# Environmental_Sensor.net
KiCad netlist of a schematic drawn in Altium Designer
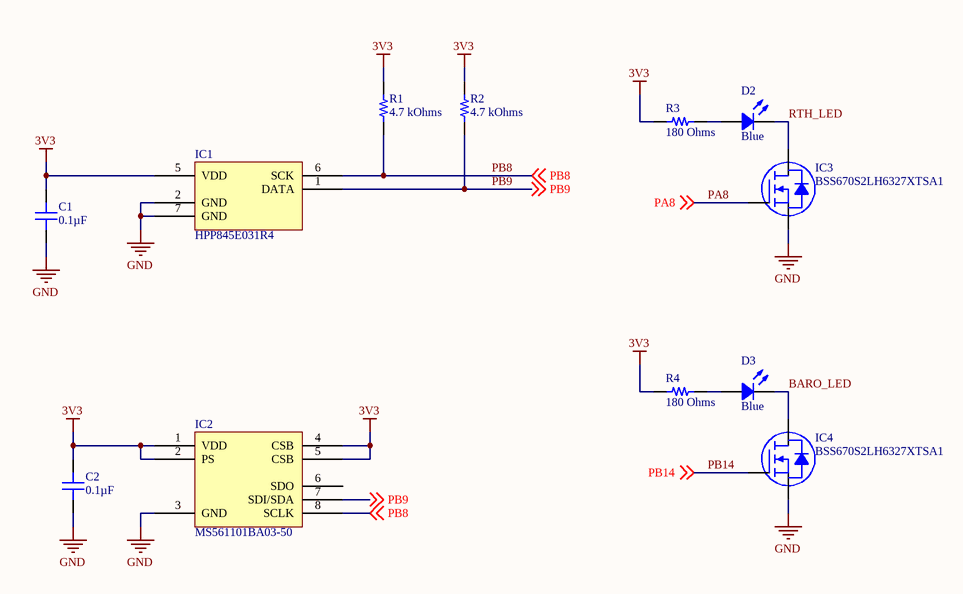
[diagram p0: Environmental Sensor.SchDoc]

(export (version "E")
  (design (tool "Eeschema 10.0.6"))
  (components
    (comp (ref "C1")
      (value "0.1µF")
      (footprint "CAP 0603_1608")
      (description "CAP CER 0.1UF 50V X7R 0603")
      (fields (field (name "PART NUMBER") "06035C104JAT4A") (field (name "MANUFACTURER") "AVX Corporation"))
      (libsource (lib "altiumlibrary.com") (part "Capacitor"))
    )
    (comp (ref "C2")
      (value "0.1µF")
      (footprint "CAP 0603_1608")
      (description "CAP CER 0.1UF 50V X7R 0603")
      (fields (field (name "PART NUMBER") "06035C104JAT4A") (field (name "MANUFACTURER") "AVX Corporation"))
      (libsource (lib "altiumlibrary.com") (part "Capacitor"))
    )
    (comp (ref "D2")
      (value "Blue")
      (footprint "LED 0603_1608 BLUE")
      (description "LED BLUE CLEAR CHIP SMD")
      (fields (field (name "PART NUMBER") "LTST-C193TBKT-5A") (field (name "MANUFACTURER") "Lite-On Inc."))
      (libsource (lib "altiumlibrary.com") (part "LED"))
    )
    (comp (ref "D3")
      (value "Blue")
      (footprint "LED 0603_1608 BLUE")
      (description "LED BLUE CLEAR CHIP SMD")
      (fields (field (name "PART NUMBER") "LTST-C193TBKT-5A") (field (name "MANUFACTURER") "Lite-On Inc."))
      (libsource (lib "altiumlibrary.com") (part "LED"))
    )
    (comp (ref "IC1")
      (value "HPP845E031R4")
      (footprint "TE HPP845E031R4")
      (description "SENSOR HUMID/TEMP 3V I2C 2% SMD")
      (fields (field (name "MANUFACTURER") "TE Connectivity Measurement Specialties"))
      (libsource (lib "altiumlibrary.com") (part "TE HPP845E031R4"))
    )
    (comp (ref "IC2")
      (value "MS561101BA03-50")
      (footprint "MEAS SPEC MS5611-01BA03")
      (description "BAROMETRIC PRESSURE SENSOR")
      (fields (field (name "MANUFACTURER") "TE Connectivity Measurement Specialties"))
      (libsource (lib "altiumlibrary.com") (part "MEAS SPEC MS5611"))
    )
    (comp (ref "IC3")
      (value "BSS670S2LH6327XTSA1")
      (footprint "INFINEON SOT-23-3")
      (description "MOSFET N-CH 55V 540MA SOT23")
      (fields (field (name "MANUFACTURER") "Infineon Technologies"))
      (libsource (lib "altiumlibrary.com") (part "INFINEON MOSFET N-CH SOT-23-3 GSD"))
    )
    (comp (ref "IC4")
      (value "BSS670S2LH6327XTSA1")
      (footprint "INFINEON SOT-23-3")
      (description "MOSFET N-CH 55V 540MA SOT23")
      (fields (field (name "MANUFACTURER") "Infineon Technologies"))
      (libsource (lib "altiumlibrary.com") (part "INFINEON MOSFET N-CH SOT-23-3 GSD"))
    )
    (comp (ref "R1")
      (value "4.7 kOhms")
      (footprint "RES 0603_1608")
      (description "RES SMD 4.7K OHM 1% 1/10W 0603")
      (fields
        (field (name "PART NUMBER") "ERJ-3EKF4701V")
        (field (name "MANUFACTURER") "Panasonic Electronic Components")
      )
      (libsource (lib "altiumlibrary.com") (part "Resistor"))
    )
    (comp (ref "R2")
      (value "4.7 kOhms")
      (footprint "RES 0603_1608")
      (description "RES SMD 4.7K OHM 1% 1/10W 0603")
      (fields
        (field (name "PART NUMBER") "ERJ-3EKF4701V")
        (field (name "MANUFACTURER") "Panasonic Electronic Components")
      )
      (libsource (lib "altiumlibrary.com") (part "Resistor"))
    )
    (comp (ref "R3")
      (value "180 Ohms")
      (footprint "RES 0603_1608")
      (description "RES SMD 180 OHM 5% 1/4W 0603")
      (fields
        (field (name "PART NUMBER") "ERJ-PA3J181V")
        (field (name "MANUFACTURER") "Panasonic Electronic Components")
      )
      (libsource (lib "altiumlibrary.com") (part "Resistor"))
    )
    (comp (ref "R4")
      (value "180 Ohms")
      (footprint "RES 0603_1608")
      (description "RES SMD 180 OHM 5% 1/4W 0603")
      (fields
        (field (name "PART NUMBER") "ERJ-PA3J181V")
        (field (name "MANUFACTURER") "Panasonic Electronic Components")
      )
      (libsource (lib "altiumlibrary.com") (part "Resistor"))
    )
  )
  (nets
    (net (code "1") (name "/BARO_LED") (class "Default")
      (node (ref "D3") (pin "2") (pinfunction "2_2") (pintype "passive"))
      (node (ref "IC4") (pin "3") (pinfunction "D_3") (pintype "passive"))
    )
    (net (code "2") (name "/RTH_LED") (class "Default")
      (node (ref "D2") (pin "2") (pinfunction "2_2") (pintype "passive"))
      (node (ref "IC3") (pin "3") (pinfunction "D_3") (pintype "passive"))
    )
    (net (code "3") (name "3V3") (class "Default")
      (node (ref "C1") (pin "2") (pinfunction "2_2") (pintype "passive"))
      (node (ref "C2") (pin "2") (pinfunction "2_2") (pintype "passive"))
      (node (ref "IC1") (pin "5") (pinfunction "VDD_5") (pintype "passive"))
      (node (ref "IC2") (pin "1") (pinfunction "VDD_1") (pintype "passive"))
      (node (ref "IC2") (pin "2") (pinfunction "PS_2") (pintype "passive"))
      (node (ref "IC2") (pin "4") (pinfunction "CSB_4") (pintype "passive"))
      (node (ref "IC2") (pin "5") (pinfunction "CSB_5") (pintype "passive"))
      (node (ref "R1") (pin "2") (pinfunction "2_2") (pintype "passive"))
      (node (ref "R2") (pin "2") (pinfunction "2_2") (pintype "passive"))
      (node (ref "R3") (pin "1") (pinfunction "1_1") (pintype "passive"))
      (node (ref "R4") (pin "1") (pinfunction "1_1") (pintype "passive"))
    )
    (net (code "4") (name "GND") (class "Default")
      (node (ref "C1") (pin "1") (pinfunction "1_1") (pintype "passive"))
      (node (ref "C2") (pin "1") (pinfunction "1_1") (pintype "passive"))
      (node (ref "IC1") (pin "2") (pinfunction "GND_2") (pintype "passive"))
      (node (ref "IC1") (pin "7") (pinfunction "GND_7") (pintype "passive"))
      (node (ref "IC2") (pin "3") (pinfunction "GND_3") (pintype "passive"))
      (node (ref "IC3") (pin "2") (pinfunction "S_2") (pintype "passive"))
      (node (ref "IC4") (pin "2") (pinfunction "S_2") (pintype "passive"))
    )
    (net (code "5") (name "Net-(D2-Pad1)") (class "Default")
      (node (ref "D2") (pin "1") (pinfunction "1_1") (pintype "passive"))
      (node (ref "R3") (pin "2") (pinfunction "2_2") (pintype "passive"))
    )
    (net (code "6") (name "Net-(D3-Pad1)") (class "Default")
      (node (ref "D3") (pin "1") (pinfunction "1_1") (pintype "passive"))
      (node (ref "R4") (pin "2") (pinfunction "2_2") (pintype "passive"))
    )
    (net (code "7") (name "PA8") (class "Default")
      (node (ref "IC3") (pin "1") (pinfunction "G_1") (pintype "passive"))
    )
    (net (code "8") (name "PB8") (class "Default")
      (node (ref "IC1") (pin "6") (pinfunction "SCK_6") (pintype "passive"))
      (node (ref "IC2") (pin "8") (pinfunction "SCLK_8") (pintype "passive"))
      (node (ref "R1") (pin "1") (pinfunction "1_1") (pintype "passive"))
    )
    (net (code "9") (name "PB9") (class "Default")
      (node (ref "IC1") (pin "1") (pinfunction "DATA_1") (pintype "passive"))
      (node (ref "IC2") (pin "7") (pinfunction "SDI/SDA_7") (pintype "passive"))
      (node (ref "R2") (pin "1") (pinfunction "1_1") (pintype "passive"))
    )
    (net (code "10") (name "PB14") (class "Default")
      (node (ref "IC4") (pin "1") (pinfunction "G_1") (pintype "passive"))
    )
    (net (code "11") (name "unconnected-(IC2-SDO-Pad6)") (class "Default")
      (node (ref "IC2") (pin "6") (pinfunction "SDO_6") (pintype "passive"))
    )
  )
)
